# psu.net
KiCad netlist of a schematic drawn in EAGLE
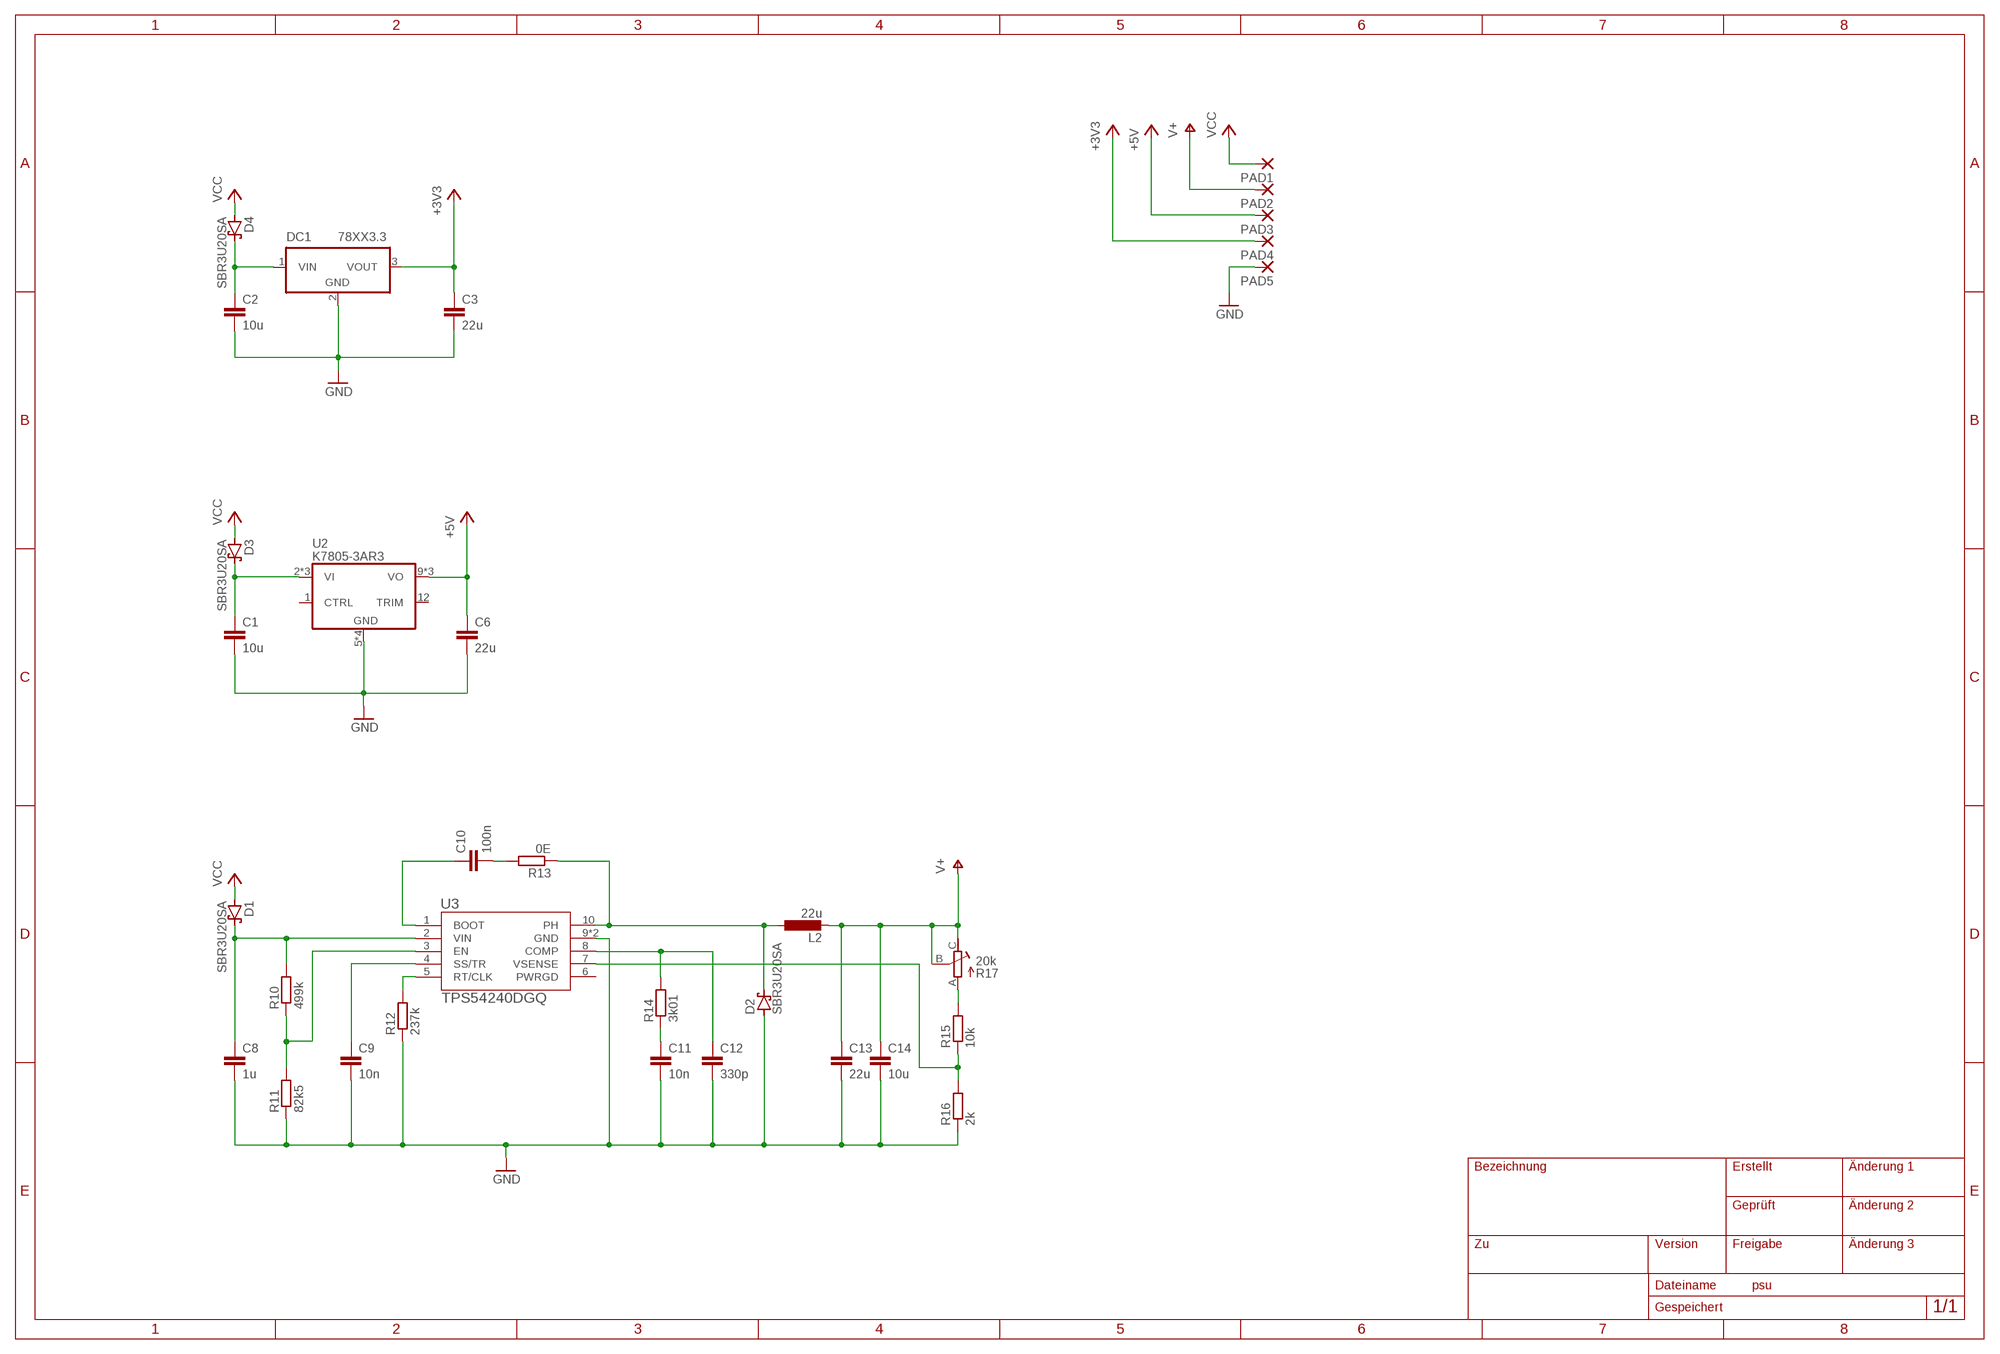
[diagram p0: schematic, sheet 1]

(export (version "E")
  (design (tool "Eeschema 10.0.6"))
  (components
    (comp (ref "C1")
      (value "10u")
      (footprint "eagle-import:C0805")
      (libsource (lib "eagle-import") (part "C-EUC0805"))
    )
    (comp (ref "C2")
      (value "10u")
      (footprint "eagle-import:C0805")
      (libsource (lib "eagle-import") (part "C-EUC0805"))
    )
    (comp (ref "C3")
      (value "22u")
      (footprint "eagle-import:C0805")
      (libsource (lib "eagle-import") (part "C-EUC0805"))
    )
    (comp (ref "C6")
      (value "22u")
      (footprint "eagle-import:C0805")
      (libsource (lib "eagle-import") (part "C-EUC0805"))
    )
    (comp (ref "C8")
      (value "1u")
      (footprint "eagle-import:C0805")
      (libsource (lib "eagle-import") (part "C-EUC0805"))
    )
    (comp (ref "C9")
      (value "10n")
      (footprint "eagle-import:C0603")
      (libsource (lib "eagle-import") (part "C-EUC0603"))
    )
    (comp (ref "C10")
      (value "100n")
      (footprint "eagle-import:C0603")
      (libsource (lib "eagle-import") (part "C-EUC0603"))
    )
    (comp (ref "C11")
      (value "10n")
      (footprint "eagle-import:C0603")
      (libsource (lib "eagle-import") (part "C-EUC0603"))
    )
    (comp (ref "C12")
      (value "330p")
      (footprint "eagle-import:C0603")
      (libsource (lib "eagle-import") (part "C-EUC0603"))
    )
    (comp (ref "C13")
      (value "22u")
      (footprint "eagle-import:C0805")
      (libsource (lib "eagle-import") (part "C-EUC0805"))
    )
    (comp (ref "C14")
      (value "10u")
      (footprint "eagle-import:C0603")
      (libsource (lib "eagle-import") (part "C-EUC0603"))
    )
    (comp (ref "D1")
      (value "SBR3U20SA")
      (footprint "eagle-import:SMA")
      (libsource (lib "eagle-import") (part "DIODE-SCHOTTKY-SMA"))
    )
    (comp (ref "D2")
      (value "SBR3U20SA")
      (footprint "eagle-import:SMA")
      (libsource (lib "eagle-import") (part "DIODE-SCHOTTKY-SMA"))
    )
    (comp (ref "D3")
      (value "SBR3U20SA")
      (footprint "eagle-import:SMA")
      (libsource (lib "eagle-import") (part "DIODE-SCHOTTKY-SMA"))
    )
    (comp (ref "D4")
      (value "SBR3U20SA")
      (footprint "eagle-import:SMA")
      (libsource (lib "eagle-import") (part "DIODE-SCHOTTKY-SMA"))
    )
    (comp (ref "DC1")
      (value "78XX3.3")
      (footprint "eagle-import:SIP3")
      (libsource (lib "eagle-import") (part "78XX3.3"))
    )
    (comp (ref "L2")
      (value "22u")
      (footprint "eagle-import:ETQP4M")
      (libsource (lib "eagle-import") (part "SPULE11.7X11"))
    )
    (comp (ref "PAD1")
      (value "WIREPAD2,54/1,1")
      (footprint "eagle-import:2,54_1,1")
      (libsource (lib "eagle-import") (part "WIREPAD2,54/1,1"))
    )
    (comp (ref "PAD2")
      (value "WIREPAD2,54/1,1")
      (footprint "eagle-import:2,54_1,1")
      (libsource (lib "eagle-import") (part "WIREPAD2,54/1,1"))
    )
    (comp (ref "PAD3")
      (value "WIREPAD2,54/1,1")
      (footprint "eagle-import:2,54_1,1")
      (libsource (lib "eagle-import") (part "WIREPAD2,54/1,1"))
    )
    (comp (ref "PAD4")
      (value "WIREPAD2,54/1,1")
      (footprint "eagle-import:2,54_1,1")
      (libsource (lib "eagle-import") (part "WIREPAD2,54/1,1"))
    )
    (comp (ref "PAD5")
      (value "WIREPAD2,54/1,1")
      (footprint "eagle-import:2,54_1,1")
      (libsource (lib "eagle-import") (part "WIREPAD2,54/1,1"))
    )
    (comp (ref "R10")
      (value "499k")
      (footprint "eagle-import:R0603")
      (libsource (lib "eagle-import") (part "R-EU_R0603"))
    )
    (comp (ref "R11")
      (value "82k5")
      (footprint "eagle-import:R0603")
      (libsource (lib "eagle-import") (part "R-EU_R0603"))
    )
    (comp (ref "R12")
      (value "237k")
      (footprint "eagle-import:R0603")
      (libsource (lib "eagle-import") (part "R-EU_R0603"))
    )
    (comp (ref "R13")
      (value "0E")
      (footprint "eagle-import:R0603")
      (libsource (lib "eagle-import") (part "R-EU_R0603"))
    )
    (comp (ref "R14")
      (value "3k01")
      (footprint "eagle-import:R0603")
      (libsource (lib "eagle-import") (part "R-EU_R0603"))
    )
    (comp (ref "R15")
      (value "10k")
      (footprint "eagle-import:R0603")
      (libsource (lib "eagle-import") (part "R-EU_R0603"))
    )
    (comp (ref "R16")
      (value "2k")
      (footprint "eagle-import:R0603")
      (libsource (lib "eagle-import") (part "R-EU_R0603"))
    )
    (comp (ref "R17")
      (value "20k")
      (footprint "eagle-import:TS53YL")
      (libsource (lib "eagle-import") (part "TRIMMERTS53YL-"))
    )
    (comp (ref "U2")
      (value "K7805-3AR3")
      (footprint "eagle-import:K78XX-3AR3")
      (libsource (lib "eagle-import") (part "K78XX-3AR3"))
    )
    (comp (ref "U3")
      (value "TPS54240DGQ")
      (footprint "eagle-import:HVSSOP-10P")
      (fields
        (field (name "GENERIC_PART_NUMBER") "TPS54240")
        (field (name "MANUFACTURER") "Texas Instruments")
      )
      (libsource (lib "eagle-import") (part "TPS54240DGQ"))
    )
  )
  (nets
    (net (code "1") (name "+3V3") (class "Default")
      (node (ref "C3") (pin "1") (pinfunction "1_1") (pintype "passive"))
      (node (ref "DC1") (pin "3") (pinfunction "VOUT_3") (pintype "passive"))
      (node (ref "PAD4") (pin "1") (pinfunction "P_1") (pintype "passive"))
    )
    (net (code "2") (name "+5V") (class "Default")
      (node (ref "C6") (pin "1") (pinfunction "1_1") (pintype "passive"))
      (node (ref "PAD3") (pin "1") (pinfunction "P_1") (pintype "passive"))
      (node (ref "U2") (pin "10") (pinfunction "VO_10") (pintype "passive"))
      (node (ref "U2") (pin "11") (pinfunction "VO_11") (pintype "passive"))
      (node (ref "U2") (pin "9") (pinfunction "VO_9") (pintype "passive"))
    )
    (net (code "3") (name "GND") (class "Default")
      (node (ref "C1") (pin "2") (pinfunction "2_2") (pintype "passive"))
      (node (ref "C11") (pin "2") (pinfunction "2_2") (pintype "passive"))
      (node (ref "C12") (pin "2") (pinfunction "2_2") (pintype "passive"))
      (node (ref "C13") (pin "2") (pinfunction "2_2") (pintype "passive"))
      (node (ref "C14") (pin "2") (pinfunction "2_2") (pintype "passive"))
      (node (ref "C2") (pin "2") (pinfunction "2_2") (pintype "passive"))
      (node (ref "C3") (pin "2") (pinfunction "2_2") (pintype "passive"))
      (node (ref "C6") (pin "2") (pinfunction "2_2") (pintype "passive"))
      (node (ref "C8") (pin "2") (pinfunction "2_2") (pintype "passive"))
      (node (ref "C9") (pin "2") (pinfunction "2_2") (pintype "passive"))
      (node (ref "D2") (pin "A") (pinfunction "A_A") (pintype "passive"))
      (node (ref "DC1") (pin "2") (pinfunction "GND_2") (pintype "passive"))
      (node (ref "PAD5") (pin "1") (pinfunction "P_1") (pintype "passive"))
      (node (ref "R11") (pin "1") (pinfunction "1_1") (pintype "passive"))
      (node (ref "R12") (pin "1") (pinfunction "1_1") (pintype "passive"))
      (node (ref "R16") (pin "1") (pinfunction "1_1") (pintype "passive"))
      (node (ref "U2") (pin "5") (pinfunction "GND_5") (pintype "passive"))
      (node (ref "U2") (pin "6") (pinfunction "GND_6") (pintype "passive"))
      (node (ref "U2") (pin "7") (pinfunction "GND_7") (pintype "passive"))
      (node (ref "U2") (pin "8") (pinfunction "GND_8") (pintype "passive"))
      (node (ref "U3") (pin "11") (pinfunction "GND_11") (pintype "power_in"))
      (node (ref "U3") (pin "9") (pinfunction "GND_9") (pintype "power_in"))
    )
    (net (code "4") (name "Net-(C1-Pad1)") (class "Default")
      (node (ref "C1") (pin "1") (pinfunction "1_1") (pintype "passive"))
      (node (ref "D3") (pin "C") (pinfunction "C_C") (pintype "passive"))
      (node (ref "U2") (pin "2") (pinfunction "VI_2") (pintype "input"))
      (node (ref "U2") (pin "3") (pinfunction "VI_3") (pintype "input"))
      (node (ref "U2") (pin "4") (pinfunction "VI_4") (pintype "input"))
    )
    (net (code "5") (name "Net-(C10-Pad2)") (class "Default")
      (node (ref "C10") (pin "2") (pinfunction "2_2") (pintype "passive"))
      (node (ref "R13") (pin "2") (pinfunction "2_2") (pintype "passive"))
    )
    (net (code "6") (name "Net-(C11-Pad1)") (class "Default")
      (node (ref "C11") (pin "1") (pinfunction "1_1") (pintype "passive"))
      (node (ref "R14") (pin "1") (pinfunction "1_1") (pintype "passive"))
    )
    (net (code "7") (name "Net-(DC1-VIN)") (class "Default")
      (node (ref "C2") (pin "1") (pinfunction "1_1") (pintype "passive"))
      (node (ref "D4") (pin "C") (pinfunction "C_C") (pintype "passive"))
      (node (ref "DC1") (pin "1") (pinfunction "VIN_1") (pintype "passive"))
    )
    (net (code "8") (name "Net-(R15-Pad2)") (class "Default")
      (node (ref "R15") (pin "2") (pinfunction "2_2") (pintype "passive"))
      (node (ref "R17") (pin "A") (pinfunction "A_A") (pintype "passive"))
    )
    (net (code "9") (name "Net-(U3-BOOT)") (class "Default")
      (node (ref "C10") (pin "1") (pinfunction "1_1") (pintype "passive"))
      (node (ref "U3") (pin "1") (pinfunction "BOOT_1") (pintype "output"))
    )
    (net (code "10") (name "Net-(U3-COMP)") (class "Default")
      (node (ref "C12") (pin "1") (pinfunction "1_1") (pintype "passive"))
      (node (ref "R14") (pin "2") (pinfunction "2_2") (pintype "passive"))
      (node (ref "U3") (pin "8") (pinfunction "COMP_8") (pintype "output"))
    )
    (net (code "11") (name "Net-(U3-EN)") (class "Default")
      (node (ref "R10") (pin "1") (pinfunction "1_1") (pintype "passive"))
      (node (ref "R11") (pin "2") (pinfunction "2_2") (pintype "passive"))
      (node (ref "U3") (pin "3") (pinfunction "EN_3") (pintype "input"))
    )
    (net (code "12") (name "Net-(U3-PH)") (class "Default")
      (node (ref "D2") (pin "C") (pinfunction "C_C") (pintype "passive"))
      (node (ref "L2") (pin "1") (pinfunction "1_1") (pintype "passive"))
      (node (ref "R13") (pin "1") (pinfunction "1_1") (pintype "passive"))
      (node (ref "U3") (pin "10") (pinfunction "PH_10") (pintype "input"))
    )
    (net (code "13") (name "Net-(U3-RT{slash}CLK)") (class "Default")
      (node (ref "R12") (pin "2") (pinfunction "2_2") (pintype "passive"))
      (node (ref "U3") (pin "5") (pinfunction "RT/CLK_5") (pintype "input"))
    )
    (net (code "14") (name "Net-(U3-SS{slash}TR)") (class "Default")
      (node (ref "C9") (pin "1") (pinfunction "1_1") (pintype "passive"))
      (node (ref "U3") (pin "4") (pinfunction "SS/TR_4") (pintype "input"))
    )
    (net (code "15") (name "Net-(U3-VIN)") (class "Default")
      (node (ref "C8") (pin "1") (pinfunction "1_1") (pintype "passive"))
      (node (ref "D1") (pin "C") (pinfunction "C_C") (pintype "passive"))
      (node (ref "R10") (pin "2") (pinfunction "2_2") (pintype "passive"))
      (node (ref "U3") (pin "2") (pinfunction "VIN_2") (pintype "input"))
    )
    (net (code "16") (name "Net-(U3-VSENSE)") (class "Default")
      (node (ref "R15") (pin "1") (pinfunction "1_1") (pintype "passive"))
      (node (ref "R16") (pin "2") (pinfunction "2_2") (pintype "passive"))
      (node (ref "U3") (pin "7") (pinfunction "VSENSE_7") (pintype "input"))
    )
    (net (code "17") (name "V+") (class "Default")
      (node (ref "C13") (pin "1") (pinfunction "1_1") (pintype "passive"))
      (node (ref "C14") (pin "1") (pinfunction "1_1") (pintype "passive"))
      (node (ref "L2") (pin "2") (pinfunction "2_2") (pintype "passive"))
      (node (ref "PAD2") (pin "1") (pinfunction "P_1") (pintype "passive"))
      (node (ref "R17") (pin "B") (pinfunction "S_B") (pintype "passive"))
      (node (ref "R17") (pin "C") (pinfunction "E_C") (pintype "passive"))
    )
    (net (code "18") (name "VCC") (class "Default")
      (node (ref "D1") (pin "A") (pinfunction "A_A") (pintype "passive"))
      (node (ref "D3") (pin "A") (pinfunction "A_A") (pintype "passive"))
      (node (ref "D4") (pin "A") (pinfunction "A_A") (pintype "passive"))
      (node (ref "PAD1") (pin "1") (pinfunction "P_1") (pintype "passive"))
    )
    (net (code "19") (name "unconnected-(U2-CTRL-Pad1)") (class "Default")
      (node (ref "U2") (pin "1") (pinfunction "CTRL_1") (pintype "input"))
    )
    (net (code "20") (name "unconnected-(U2-TRIM-Pad12)") (class "Default")
      (node (ref "U2") (pin "12") (pinfunction "TRIM_12") (pintype "input"))
    )
    (net (code "21") (name "unconnected-(U3-PWRGD-Pad6)") (class "Default")
      (node (ref "U3") (pin "6") (pinfunction "PWRGD_6") (pintype "output"))
    )
  )
)
